# controls.net
KiCad netlist of a schematic drawn in EAGLE
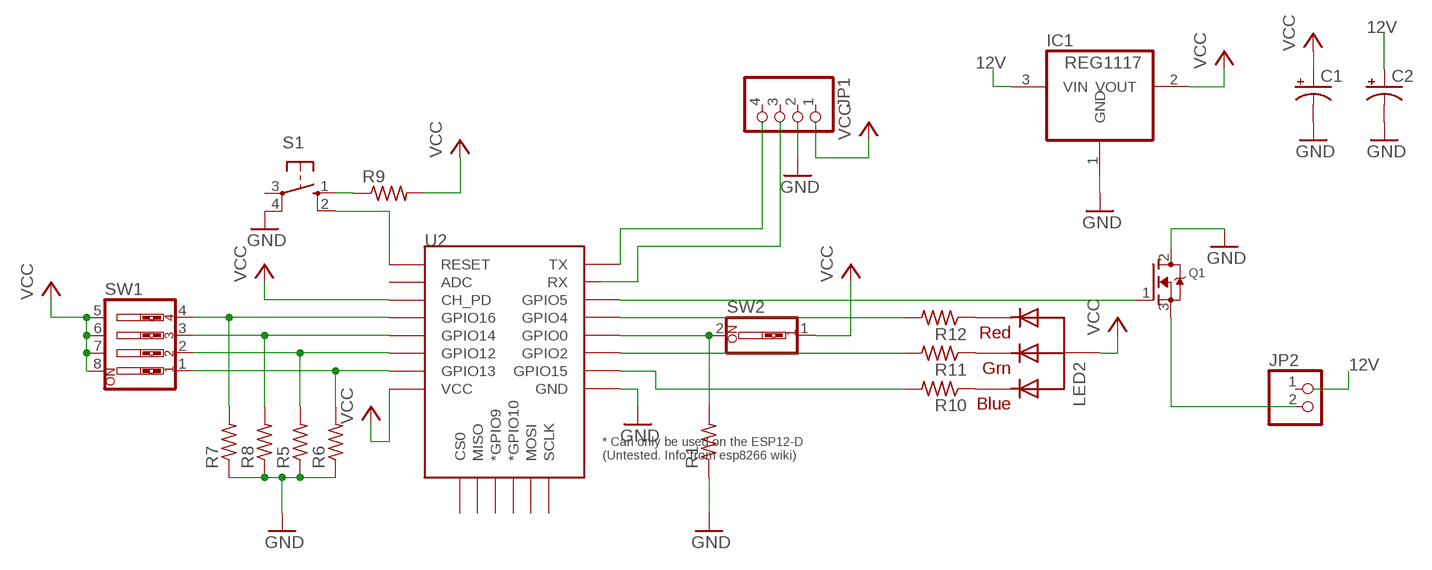
[diagram p0: schematic, sheet 1]

(export (version "E")
  (design (tool "Eeschema 10.0.6"))
  (components
    (comp (ref "C1")
      (value "CPOL-USE2,5-6E")
      (footprint "eagle-import:E2,5-6E")
      (libsource (lib "eagle-import") (part "CPOL-USE2,5-6E"))
    )
    (comp (ref "C2")
      (value "CPOL-USE2,5-6E")
      (footprint "eagle-import:E2,5-6E")
      (libsource (lib "eagle-import") (part "CPOL-USE2,5-6E"))
    )
    (comp (ref "IC1")
      (value "REG1117")
      (footprint "eagle-import:SOT223")
      (libsource (lib "eagle-import") (part "REG1117"))
    )
    (comp (ref "JP1")
      (value "PINHD-1X4")
      (footprint "eagle-import:1X04")
      (libsource (lib "eagle-import") (part "PINHD-1X4"))
    )
    (comp (ref "JP2")
      (value "PINHD-1X2")
      (footprint "eagle-import:1X02")
      (libsource (lib "eagle-import") (part "PINHD-1X2"))
    )
    (comp (ref "LED2")
      (value "RGBLED_CA-5MM")
      (footprint "eagle-import:LED5MMRGB")
      (libsource (lib "eagle-import") (part "RGBLED_CA-5MM"))
    )
    (comp (ref "Q1")
      (value "MOSFET-NGDS_TO220V")
      (footprint "eagle-import:TO220V")
      (libsource (lib "eagle-import") (part "MOSFET-NGDS_TO220V"))
    )
    (comp (ref "R1")
      (value "R-US_0207/12")
      (footprint "eagle-import:0207_12")
      (libsource (lib "eagle-import") (part "R-US_0207/12"))
    )
    (comp (ref "R5")
      (value "R-US_0207/12")
      (footprint "eagle-import:0207_12")
      (libsource (lib "eagle-import") (part "R-US_0207/12"))
    )
    (comp (ref "R6")
      (value "R-US_0207/12")
      (footprint "eagle-import:0207_12")
      (libsource (lib "eagle-import") (part "R-US_0207/12"))
    )
    (comp (ref "R7")
      (value "R-US_0207/12")
      (footprint "eagle-import:0207_12")
      (libsource (lib "eagle-import") (part "R-US_0207/12"))
    )
    (comp (ref "R8")
      (value "R-US_0207/12")
      (footprint "eagle-import:0207_12")
      (libsource (lib "eagle-import") (part "R-US_0207/12"))
    )
    (comp (ref "R9")
      (value "R-US_0207/12")
      (footprint "eagle-import:0207_12")
      (libsource (lib "eagle-import") (part "R-US_0207/12"))
    )
    (comp (ref "R10")
      (value "R-US_0207/12")
      (footprint "eagle-import:0207_12")
      (libsource (lib "eagle-import") (part "R-US_0207/12"))
    )
    (comp (ref "R11")
      (value "R-US_0207/12")
      (footprint "eagle-import:0207_12")
      (libsource (lib "eagle-import") (part "R-US_0207/12"))
    )
    (comp (ref "R12")
      (value "R-US_0207/12")
      (footprint "eagle-import:0207_12")
      (libsource (lib "eagle-import") (part "R-US_0207/12"))
    )
    (comp (ref "S1")
      (value "10-XX")
      (footprint "eagle-import:B3F-10XX")
      (fields (field (name "MPN") "B3F-1000"))
      (libsource (lib "eagle-import") (part "10-XX"))
    )
    (comp (ref "SW1")
      (value "SW_DIP-4")
      (footprint "eagle-import:EDG-04")
      (libsource (lib "eagle-import") (part "SW_DIP-4"))
    )
    (comp (ref "SW2")
      (value "SW_DIP-1")
      (footprint "eagle-import:EDG-01")
      (libsource (lib "eagle-import") (part "SW_DIP-1"))
    )
    (comp (ref "U2")
      (value "ESP12ESMD")
      (footprint "eagle-import:ESP12E-SMD")
      (libsource (lib "eagle-import") (part "ESP12ESMD"))
    )
  )
  (nets
    (net (code "1") (name "/12V") (class "Default")
      (node (ref "IC1") (pin "3") (pinfunction "VIN_3") (pintype "input"))
    )
    (net (code "2") (name "GND") (class "Default")
      (node (ref "C1") (pin "-") (pinfunction "-_-") (pintype "passive"))
      (node (ref "C2") (pin "-") (pinfunction "-_-") (pintype "passive"))
      (node (ref "IC1") (pin "1") (pinfunction "GND_1") (pintype "power_in"))
      (node (ref "Q1") (pin "2") (pinfunction "D_2") (pintype "bidirectional"))
      (node (ref "R1") (pin "1") (pinfunction "1_1") (pintype "passive"))
      (node (ref "R5") (pin "1") (pinfunction "1_1") (pintype "passive"))
      (node (ref "R6") (pin "1") (pinfunction "1_1") (pintype "passive"))
      (node (ref "R7") (pin "1") (pinfunction "1_1") (pintype "passive"))
      (node (ref "R8") (pin "1") (pinfunction "1_1") (pintype "passive"))
      (node (ref "S1") (pin "4") (pinfunction "P1_4") (pintype "passive"))
      (node (ref "U2") (pin "GND") (pinfunction "GND_GND") (pintype "bidirectional"))
    )
    (net (code "3") (name "Net-(LED2-BLUE)") (class "Default")
      (node (ref "LED2") (pin "4") (pinfunction "BLUE_4") (pintype "bidirectional"))
      (node (ref "R10") (pin "1") (pinfunction "1_1") (pintype "passive"))
    )
    (net (code "4") (name "Net-(LED2-GREEN)") (class "Default")
      (node (ref "LED2") (pin "3") (pinfunction "GREEN_3") (pintype "bidirectional"))
      (node (ref "R11") (pin "1") (pinfunction "1_1") (pintype "passive"))
    )
    (net (code "5") (name "Net-(LED2-RED)") (class "Default")
      (node (ref "LED2") (pin "1") (pinfunction "RED_1") (pintype "bidirectional"))
      (node (ref "R12") (pin "1") (pinfunction "1_1") (pintype "passive"))
    )
    (net (code "6") (name "Net-(Q1-G)") (class "Default")
      (node (ref "Q1") (pin "1") (pinfunction "G_1") (pintype "bidirectional"))
      (node (ref "U2") (pin "GPIO5") (pinfunction "GPIO5_GPIO5") (pintype "bidirectional"))
    )
    (net (code "7") (name "Net-(Q1-S)") (class "Default")
      (node (ref "JP2") (pin "2") (pinfunction "2_2") (pintype "passive"))
      (node (ref "Q1") (pin "3") (pinfunction "S_3") (pintype "bidirectional"))
    )
    (net (code "8") (name "Net-(R1-Pad2)") (class "Default")
      (node (ref "R1") (pin "2") (pinfunction "2_2") (pintype "passive"))
      (node (ref "SW2") (pin "2") (pinfunction "2_2") (pintype "passive"))
      (node (ref "U2") (pin "GPIO0") (pinfunction "GPIO0_GPIO0") (pintype "bidirectional"))
    )
    (net (code "9") (name "Net-(R5-Pad2)") (class "Default")
      (node (ref "R5") (pin "2") (pinfunction "2_2") (pintype "passive"))
      (node (ref "SW1") (pin "2") (pinfunction "2_2") (pintype "passive"))
      (node (ref "U2") (pin "GPIO12") (pinfunction "GPIO12_GPIO12") (pintype "bidirectional"))
    )
    (net (code "10") (name "Net-(R6-Pad2)") (class "Default")
      (node (ref "R6") (pin "2") (pinfunction "2_2") (pintype "passive"))
      (node (ref "SW1") (pin "1") (pinfunction "1_1") (pintype "passive"))
      (node (ref "U2") (pin "GPIO13") (pinfunction "GPIO13_GPIO13") (pintype "bidirectional"))
    )
    (net (code "11") (name "Net-(R7-Pad2)") (class "Default")
      (node (ref "R7") (pin "2") (pinfunction "2_2") (pintype "passive"))
      (node (ref "SW1") (pin "4") (pinfunction "4_4") (pintype "passive"))
      (node (ref "U2") (pin "GPIO16") (pinfunction "GPIO16_GPIO16") (pintype "bidirectional"))
    )
    (net (code "12") (name "Net-(R8-Pad2)") (class "Default")
      (node (ref "R8") (pin "2") (pinfunction "2_2") (pintype "passive"))
      (node (ref "SW1") (pin "3") (pinfunction "3_3") (pintype "passive"))
      (node (ref "U2") (pin "GPIO14") (pinfunction "GPIO14_GPIO14") (pintype "bidirectional"))
    )
    (net (code "13") (name "Net-(R10-Pad2)") (class "Default")
      (node (ref "R10") (pin "2") (pinfunction "2_2") (pintype "passive"))
      (node (ref "U2") (pin "GPIO15") (pinfunction "GPIO15_GPIO15") (pintype "bidirectional"))
    )
    (net (code "14") (name "Net-(R11-Pad2)") (class "Default")
      (node (ref "R11") (pin "2") (pinfunction "2_2") (pintype "passive"))
      (node (ref "U2") (pin "GPIO2") (pinfunction "GPIO2_GPIO2") (pintype "bidirectional"))
    )
    (net (code "15") (name "Net-(R12-Pad2)") (class "Default")
      (node (ref "R12") (pin "2") (pinfunction "2_2") (pintype "passive"))
      (node (ref "U2") (pin "GPIO4") (pinfunction "GPIO4_GPIO4") (pintype "bidirectional"))
    )
    (net (code "16") (name "Net-(S1-S)") (class "Default")
      (node (ref "R9") (pin "1") (pinfunction "1_1") (pintype "passive"))
      (node (ref "S1") (pin "1") (pinfunction "S_1") (pintype "passive"))
    )
    (net (code "17") (name "Net-(S1-S1)") (class "Default")
      (node (ref "S1") (pin "2") (pinfunction "S1_2") (pintype "passive"))
      (node (ref "U2") (pin "RESET") (pinfunction "RESET_RESET") (pintype "bidirectional"))
    )
    (net (code "18") (name "VCC") (class "Default")
      (node (ref "C1") (pin "+") (pinfunction "+_+") (pintype "passive"))
      (node (ref "IC1") (pin "2") (pinfunction "VOUT_2") (pintype "output"))
      (node (ref "LED2") (pin "2") (pinfunction "VCC_2") (pintype "bidirectional"))
      (node (ref "R9") (pin "2") (pinfunction "2_2") (pintype "passive"))
      (node (ref "SW1") (pin "5") (pinfunction "5_5") (pintype "passive"))
      (node (ref "SW1") (pin "6") (pinfunction "6_6") (pintype "passive"))
      (node (ref "SW1") (pin "7") (pinfunction "7_7") (pintype "passive"))
      (node (ref "SW1") (pin "8") (pinfunction "8_8") (pintype "passive"))
      (node (ref "SW2") (pin "1") (pinfunction "1_1") (pintype "passive"))
      (node (ref "U2") (pin "CH_PD") (pinfunction "CH_PD_CH_PD") (pintype "bidirectional"))
      (node (ref "U2") (pin "VCC") (pinfunction "VCC_VCC") (pintype "bidirectional"))
    )
    (net (code "19") (name "unconnected-(C2-Pad+)") (class "Default")
      (node (ref "C2") (pin "+") (pinfunction "+_+") (pintype "passive"))
    )
    (net (code "20") (name "unconnected-(JP1-Pad1)") (class "Default")
      (node (ref "JP1") (pin "1") (pinfunction "1_1") (pintype "passive"))
    )
    (net (code "21") (name "unconnected-(JP1-Pad2)") (class "Default")
      (node (ref "JP1") (pin "2") (pinfunction "2_2") (pintype "passive"))
    )
    (net (code "22") (name "unconnected-(JP1-Pad3)") (class "Default")
      (node (ref "JP1") (pin "3") (pinfunction "3_3") (pintype "passive"))
    )
    (net (code "23") (name "unconnected-(JP1-Pad4)") (class "Default")
      (node (ref "JP1") (pin "4") (pinfunction "4_4") (pintype "passive"))
    )
    (net (code "24") (name "unconnected-(JP2-Pad1)") (class "Default")
      (node (ref "JP2") (pin "1") (pinfunction "1_1") (pintype "passive"))
    )
    (net (code "25") (name "unconnected-(S1-P-Pad3)") (class "Default")
      (node (ref "S1") (pin "3") (pinfunction "P_3") (pintype "passive"))
    )
    (net (code "26") (name "unconnected-(U2-*GPIO9-PadGPIO9)") (class "Default")
      (node (ref "U2") (pin "GPIO9") (pinfunction "*GPIO9_GPIO9") (pintype "bidirectional"))
    )
    (net (code "27") (name "unconnected-(U2-*GPIO10-PadGPIO10)") (class "Default")
      (node (ref "U2") (pin "GPIO10") (pinfunction "*GPIO10_GPIO10") (pintype "bidirectional"))
    )
    (net (code "28") (name "unconnected-(U2-PadADC)") (class "Default")
      (node (ref "U2") (pin "ADC") (pinfunction "ADC_ADC") (pintype "bidirectional"))
    )
    (net (code "29") (name "unconnected-(U2-PadCS0)") (class "Default")
      (node (ref "U2") (pin "CS0") (pinfunction "CS0_CS0") (pintype "bidirectional"))
    )
    (net (code "30") (name "unconnected-(U2-PadMISO)") (class "Default")
      (node (ref "U2") (pin "MISO") (pinfunction "MISO_MISO") (pintype "bidirectional"))
    )
    (net (code "31") (name "unconnected-(U2-PadMOSI)") (class "Default")
      (node (ref "U2") (pin "MOSI") (pinfunction "MOSI_MOSI") (pintype "bidirectional"))
    )
    (net (code "32") (name "unconnected-(U2-PadSCLK)") (class "Default")
      (node (ref "U2") (pin "SCLK") (pinfunction "SCLK_SCLK") (pintype "bidirectional"))
    )
    (net (code "33") (name "unconnected-(U2-RX-PadRXD0)") (class "Default")
      (node (ref "U2") (pin "RXD0") (pinfunction "RX_RXD0") (pintype "bidirectional"))
    )
    (net (code "34") (name "unconnected-(U2-TX-PadTXD0)") (class "Default")
      (node (ref "U2") (pin "TXD0") (pinfunction "TX_TXD0") (pintype "bidirectional"))
    )
  )
)
